# Schematic.net
KiCad netlist of a schematic drawn in Altium Designer
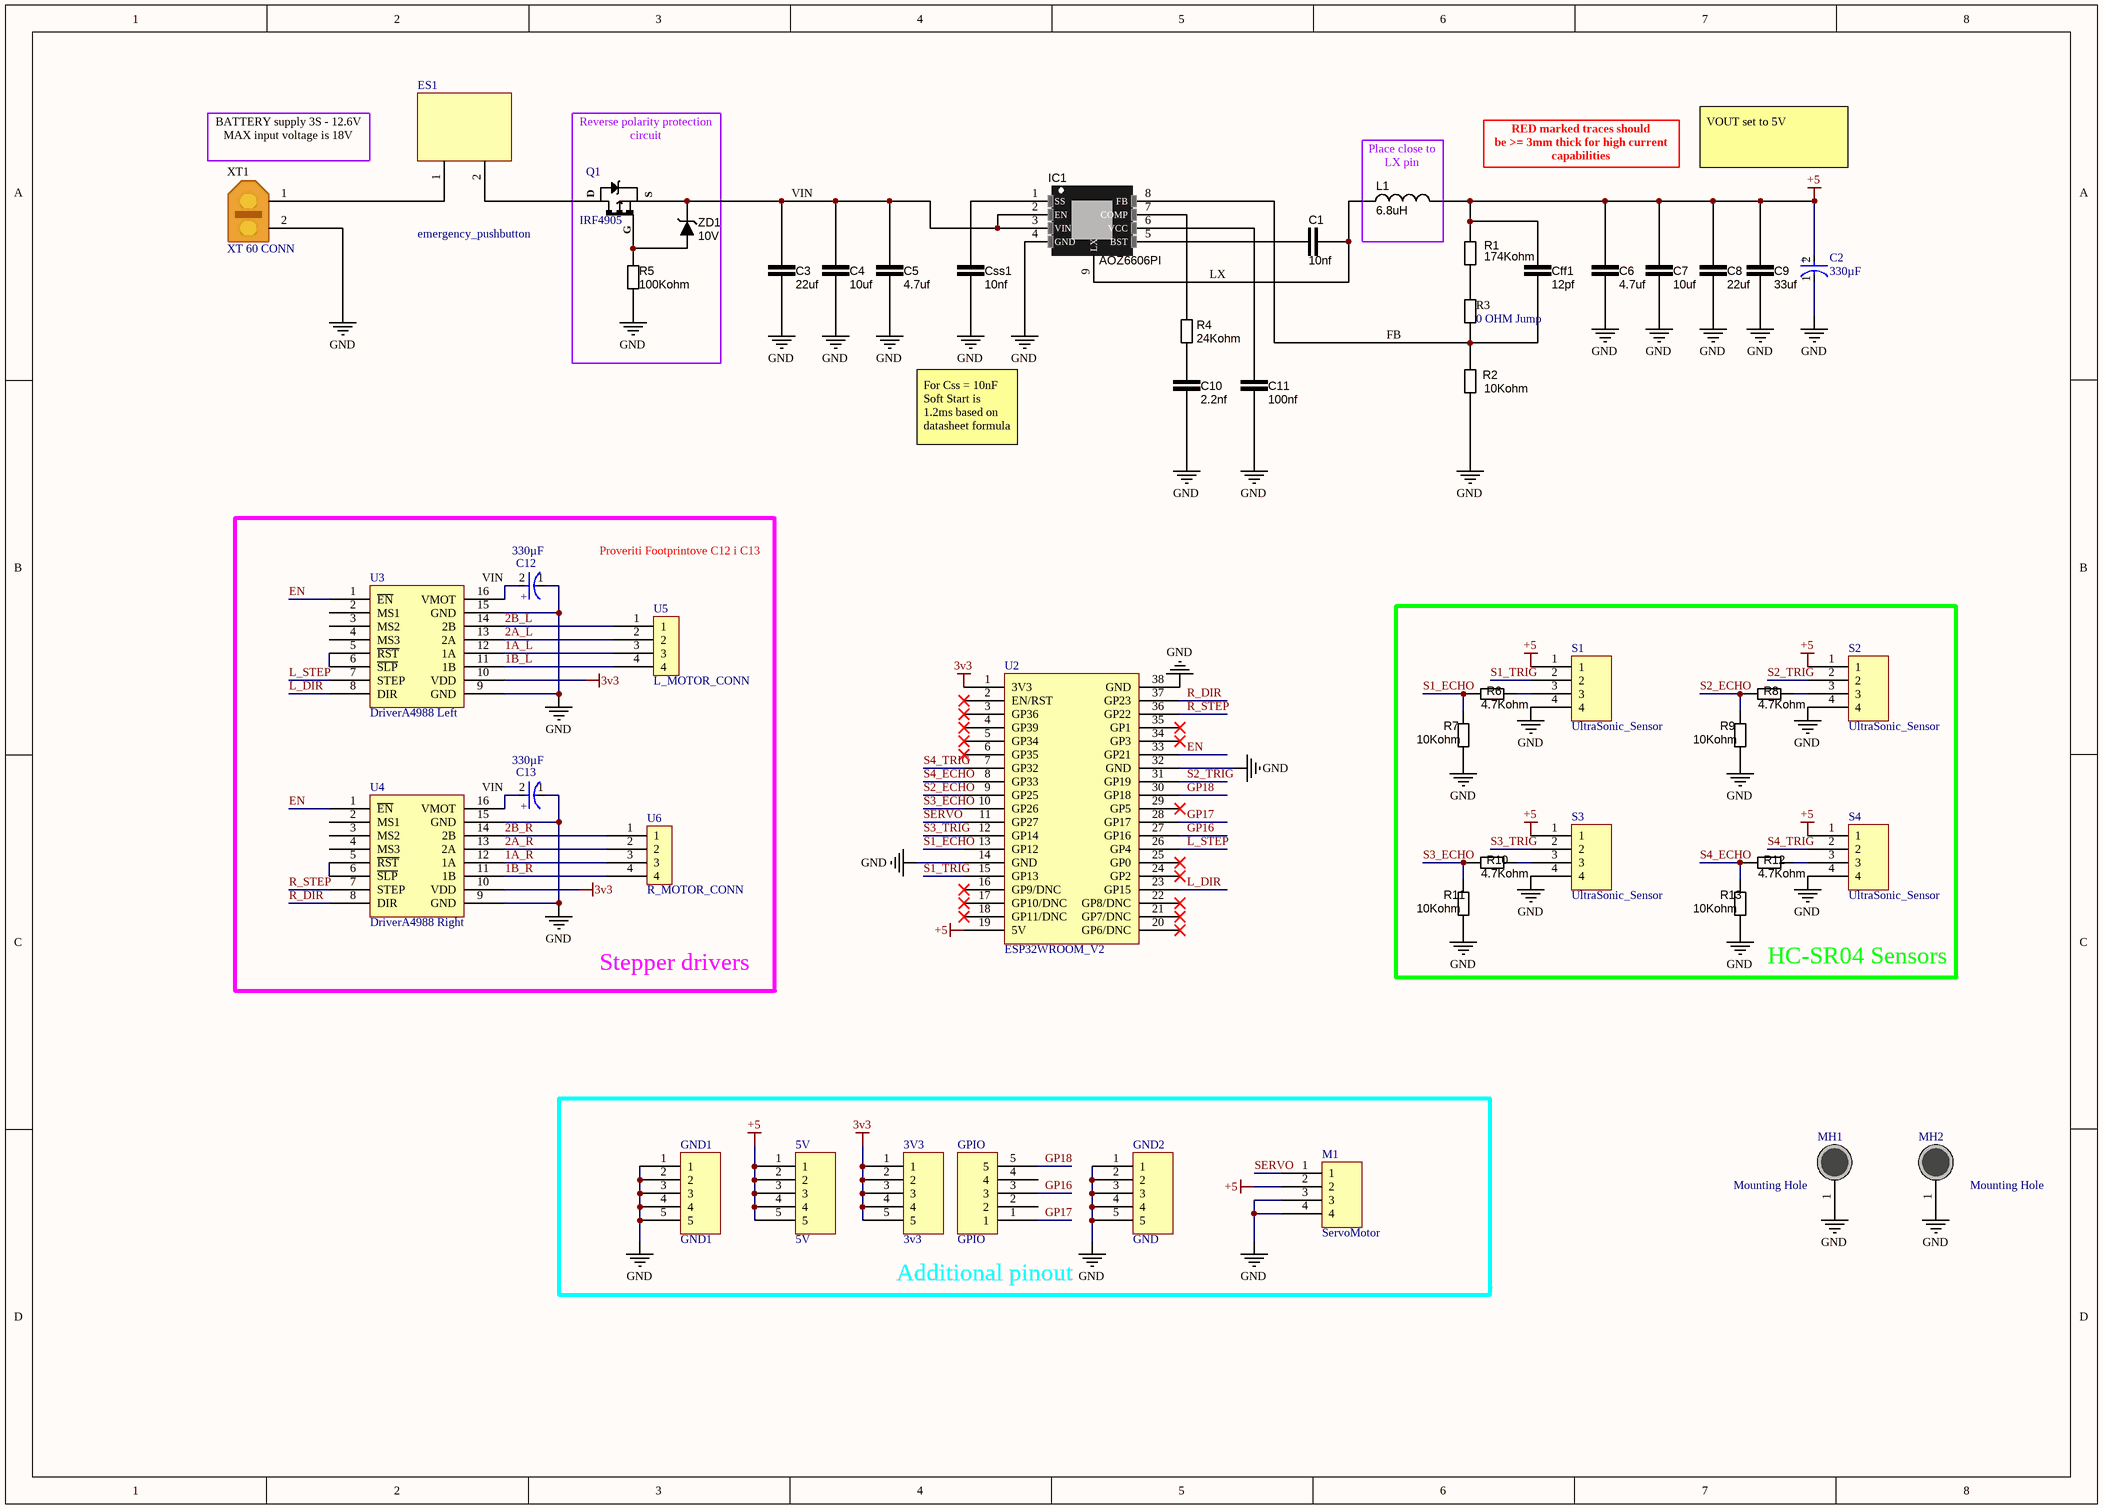
[diagram p0: Schematic.SchDoc]

(export (version "E")
  (design (tool "Eeschema 10.0.6"))
  (components
    (comp (ref "3V3")
      (value "3v3")
      (footprint "PIN_HEADER5")
      (description "5 pin header 100 mil")
      (libsource (lib "SIMA") (part "PIN_HEADER5"))
    )
    (comp (ref "5V")
      (value "5V")
      (footprint "PIN_HEADER5")
      (description "5 pin header 100 mils")
      (libsource (lib "SIMA") (part "PIN_HEADER5"))
    )
    (comp (ref "C1")
      (value "10nf")
      (footprint "CAP_0603")
      (description "CAP CER 10nF 0603 25V X7R")
      (libsource (lib "") (part "0000005_1"))
    )
    (comp (ref "C2")
      (value "330µF")
      (footprint "FP-FCG-MFG")
      (description "EEEFC1V331AP 330 uF, Aluminum Electrolytic Capacitor, 35 V, Radial Can - SMD")
      (fields (field (name "VOLTAGE") "35V") (field (name "TOLERANCE") "20%"))
      (libsource (lib "Altium Content Vault") (part "a00bbbee19879c290e62620ae7e47b1"))
    )
    (comp (ref "C3")
      (value "22uf")
      (footprint "CAP_0805")
      (description "CAP CER 22uF 0805 25V X5R")
      (libsource (lib "CapacitorsIntegrated") (part "0000001"))
    )
    (comp (ref "C4")
      (value "10uf")
      (footprint "CAP_0805")
      (description "CAP CER 10uF 0805 25V X5R")
      (libsource (lib "CapacitorsIntegrated") (part "0000002"))
    )
    (comp (ref "C5")
      (value "4.7uf")
      (footprint "CAP_0805")
      (description "CAP CER 4.7uF 0805 25V X5R")
      (libsource (lib "CapacitorsIntegrated") (part "0000003"))
    )
    (comp (ref "C6")
      (value "4.7uf")
      (footprint "CAP_0805")
      (description "CAP CER 4.7uF 0805 25V X5R")
      (libsource (lib "CapacitorsIntegrated") (part "0000003"))
    )
    (comp (ref "C7")
      (value "10uf")
      (footprint "CAP_0805")
      (description "CAP CER 10uF 0805 25V X5R")
      (libsource (lib "CapacitorsIntegrated") (part "0000002"))
    )
    (comp (ref "C8")
      (value "22uf")
      (footprint "CAP_0805")
      (description "CAP CER 22uF 0805 25V X5R")
      (libsource (lib "CapacitorsIntegrated") (part "0000001"))
    )
    (comp (ref "C9")
      (value "33uf")
      (footprint "CAP_1206")
      (description "CAP CER 33uF 1206 25V X5R")
      (libsource (lib "CapacitorsIntegrated") (part "0000004"))
    )
    (comp (ref "C10")
      (value "2.2nf")
      (footprint "CAP_0603")
      (description "CAP CER 2.2nF 0603 25V X7R")
      (libsource (lib "CapacitorsIntegrated") (part "0000006"))
    )
    (comp (ref "C11")
      (value "100nf")
      (footprint "CAP_0603")
      (description "CAP CER 100nF 0603 25V X7R")
      (libsource (lib "CapacitorsIntegrated") (part "0000007"))
    )
    (comp (ref "C12")
      (value "330µF")
      (footprint "FP-FCG-MFG")
      (description "EEEFC1V331AP 330 uF, Aluminum Electrolytic Capacitor, 35 V, Radial Can - SMD")
      (fields (field (name "VOLTAGE") "35V") (field (name "TOLERANCE") "20%"))
      (libsource (lib "Altium Content Vault") (part "a00bbbee19879c290e62620ae7e47b1"))
    )
    (comp (ref "C13")
      (value "330µF")
      (footprint "FP-FCG-MFG")
      (description "EEEFC1V331AP 330 uF, Aluminum Electrolytic Capacitor, 35 V, Radial Can - SMD")
      (fields (field (name "VOLTAGE") "35V") (field (name "TOLERANCE") "20%"))
      (libsource (lib "Altium Content Vault") (part "a00bbbee19879c290e62620ae7e47b1"))
    )
    (comp (ref "Cff1")
      (value "12pf")
      (footprint "CAP_0603")
      (description "CAP CER 12pF 0603 25V X7R")
      (libsource (lib "CapacitorsIntegrated") (part "0000008"))
    )
    (comp (ref "Css1")
      (value "10nf")
      (footprint "CAP_0603")
      (description "CAP CER 10nF 0603 25V X7R")
      (libsource (lib "CapacitorsIntegrated") (part "0000005"))
    )
    (comp (ref "ES1")
      (value "emergency_pushbutton")
      (footprint "emergency_footprint")
      (libsource (lib "SIMA") (part "emergency_pushbutton"))
    )
    (comp (ref "GND1")
      (value "GND1")
      (footprint "PIN_HEADER5")
      (description "5 pin header 100 mils")
      (libsource (lib "SIMA") (part "PIN_HEADER5"))
    )
    (comp (ref "GND2")
      (value "GND")
      (footprint "PIN_HEADER5")
      (description "5 pin header 100 mil")
      (libsource (lib "SIMA") (part "PIN_HEADER5"))
    )
    (comp (ref "GPIO")
      (value "GPIO")
      (footprint "PIN_HEADER5")
      (description "5 pin header 100 mil")
      (libsource (lib "") (part "PIN_HEADER5_1"))
    )
    (comp (ref "IC1")
      (value "AOZ6606PI")
      (footprint "SOP127P600X170_HS-9N")
      (description "Buck AOZ6606PI")
      (libsource (lib "IntegratedCircuits") (part "AOZ6606PI"))
    )
    (comp (ref "L1")
      (value "6.8uH")
      (footprint "INDM108103X40N")
      (description "IND 6.8uH 8A 23.3mOHM 13.5A ISAT")
      (libsource (lib "InductorIntegrated") (part "L000002"))
    )
    (comp (ref "M1")
      (value "ServoMotor")
      (footprint "UltraSonic_Sensor")
      (description "5 pin header 100 mil")
      (libsource (lib "SIMA") (part "UltraSonic_Sensor"))
    )
    (comp (ref "MH1")
      (value "Mounting Hole")
      (footprint "HOLE-3mm")
      (description "Mounting Hole 3mm")
      (libsource (lib "ElectroMechanical") (part "00000006"))
    )
    (comp (ref "MH2")
      (value "Mounting Hole")
      (footprint "HOLE-3mm")
      (description "Mounting Hole 3mm")
      (libsource (lib "ElectroMechanical") (part "00000006"))
    )
    (comp (ref "Q1")
      (value "IRF4905")
      (footprint "DPAK254P1524X483-3N")
      (fields
        (field (name "MANUFACTURER") "International Rectifier")
        (field (name "MANUFACTURER PART NUMBER") "IRF1404ZSPBF")
      )
      (libsource (lib "IntegratedCircuits") (part "IRF4905"))
    )
    (comp (ref "R1")
      (value "174Kohm")
      (footprint "RES_0603")
      (description "RES 174k OHM 0603 1/10W")
      (libsource (lib "ResistorsIntegrated") (part "R000003"))
    )
    (comp (ref "R2")
      (value "10Kohm")
      (footprint "RES_0603")
      (description "RES 10k OHM 0603 1/10W")
      (libsource (lib "") (part "R000001_2"))
    )
    (comp (ref "R3")
      (value "0 OHM Jump")
      (footprint "RES_0603")
      (description "RES 0 OHM JUMPER 1/10W 0603")
      (libsource (lib "ResistorsIntegrated") (part "R000007"))
    )
    (comp (ref "R4")
      (value "24Kohm")
      (footprint "RES_0603")
      (description "RES 24k OHM 0603 1/10W")
      (libsource (lib "ResistorsIntegrated") (part "R000005"))
    )
    (comp (ref "R5")
      (value "100Kohm")
      (footprint "RES_0603")
      (description "RES 100k OHM 0603 1/10W")
      (libsource (lib "ResistorsIntegrated") (part "R000006"))
    )
    (comp (ref "R6")
      (value "4.7Kohm")
      (footprint "RES_0603")
      (description "RES 4k7 OHM 0603 1/10W")
      (libsource (lib "") (part "R000001_1"))
    )
    (comp (ref "R7")
      (value "10Kohm")
      (footprint "RES_0603")
      (description "RES 10k OHM 0603 1/10W")
      (libsource (lib "ResistorsIntegrated") (part "R000001"))
    )
    (comp (ref "R8")
      (value "4.7Kohm")
      (footprint "RES_0603")
      (description "RES 4k7 OHM 0603 1/10W")
      (libsource (lib "") (part "R000001_1"))
    )
    (comp (ref "R9")
      (value "10Kohm")
      (footprint "RES_0603")
      (description "RES 10k OHM 0603 1/10W")
      (libsource (lib "ResistorsIntegrated") (part "R000001"))
    )
    (comp (ref "R10")
      (value "4.7Kohm")
      (footprint "RES_0603")
      (description "RES 4k7 OHM 0603 1/10W")
      (libsource (lib "") (part "R000001_1"))
    )
    (comp (ref "R11")
      (value "10Kohm")
      (footprint "RES_0603")
      (description "RES 10k OHM 0603 1/10W")
      (libsource (lib "ResistorsIntegrated") (part "R000001"))
    )
    (comp (ref "R12")
      (value "4.7Kohm")
      (footprint "RES_0603")
      (description "RES 4k7 OHM 0603 1/10W")
      (libsource (lib "") (part "R000001_1"))
    )
    (comp (ref "R13")
      (value "10Kohm")
      (footprint "RES_0603")
      (description "RES 10k OHM 0603 1/10W")
      (libsource (lib "ResistorsIntegrated") (part "R000001"))
    )
    (comp (ref "S1")
      (value "UltraSonic_Sensor")
      (footprint "UltraSonic_Sensor")
      (description "Connector onaj beli")
      (libsource (lib "SIMA") (part "UltraSonic_Sensor"))
    )
    (comp (ref "S2")
      (value "UltraSonic_Sensor")
      (footprint "UltraSonic_Sensor")
      (description "Connector onaj beli")
      (libsource (lib "SIMA") (part "UltraSonic_Sensor"))
    )
    (comp (ref "S3")
      (value "UltraSonic_Sensor")
      (footprint "UltraSonic_Sensor")
      (description "Connector onaj beli")
      (libsource (lib "SIMA") (part "UltraSonic_Sensor"))
    )
    (comp (ref "S4")
      (value "UltraSonic_Sensor")
      (footprint "UltraSonic_Sensor")
      (description "Connector onaj beli")
      (libsource (lib "SIMA") (part "UltraSonic_Sensor"))
    )
    (comp (ref "U2")
      (value "ESP32WROOM_V2")
      (footprint "ESP32WROOM")
      (description "Pinout Acine ESP32 Wroom plocice, pinovi poslagani po redu")
      (libsource (lib "SIMA") (part "ESP32WROOM_V2"))
    )
    (comp (ref "U3")
      (value "DriverA4988 Left")
      (footprint "DriverA4988")
      (description "Stepp Motor Driver")
      (libsource (lib "SIMA") (part "DriverA4988"))
    )
    (comp (ref "U4")
      (value "DriverA4988 Right")
      (footprint "DriverA4988")
      (description "Stepp Motor Driver")
      (libsource (lib "SIMA") (part "DriverA4988"))
    )
    (comp (ref "U5")
      (value "L_MOTOR_CONN")
      (footprint "STEP_MOTOR_CONN")
      (description "Connector onaj beli")
      (libsource (lib "SIMA") (part "STEP_MOTOR_CONN"))
    )
    (comp (ref "U6")
      (value "R_MOTOR_CONN")
      (footprint "STEP_MOTOR_CONN")
      (description "Connector onaj beli")
      (libsource (lib "SIMA") (part "STEP_MOTOR_CONN"))
    )
    (comp (ref "XT1")
      (value "XT 60 CONN")
      (footprint "XT60_CONN")
      (libsource (lib "SIMA") (part "XT60 CONN"))
    )
    (comp (ref "ZD1")
      (value "10V")
      (footprint "DIO_SMA")
      (description "Zener Diode 10 V 5 W ±5% Surface Mount SMC (DO-214AB)")
      (libsource (lib "IntegratedCircuits") (part "1SMA5931-AU_R1"))
    )
  )
  (nets
    (net (code "1") (name "+5") (class "Default")
      (node (ref "5V") (pin "1") (pinfunction "1_1") (pintype "passive"))
      (node (ref "5V") (pin "2") (pinfunction "2_2") (pintype "passive"))
      (node (ref "5V") (pin "3") (pinfunction "3_3") (pintype "passive"))
      (node (ref "5V") (pin "4") (pinfunction "4_4") (pintype "passive"))
      (node (ref "5V") (pin "5") (pinfunction "5_5") (pintype "passive"))
      (node (ref "C2") (pin "2") (pinfunction "A_2") (pintype "passive"))
      (node (ref "C6") (pin "2") (pinfunction "2_2") (pintype "passive"))
      (node (ref "C7") (pin "2") (pinfunction "2_2") (pintype "passive"))
      (node (ref "C8") (pin "2") (pinfunction "2_2") (pintype "passive"))
      (node (ref "C9") (pin "2") (pinfunction "2_2") (pintype "passive"))
      (node (ref "Cff1") (pin "2") (pinfunction "2_2") (pintype "passive"))
      (node (ref "L1") (pin "2") (pinfunction "2_2") (pintype "passive"))
      (node (ref "M1") (pin "2") (pinfunction "2_2") (pintype "passive"))
      (node (ref "R1") (pin "2") (pinfunction "2_2") (pintype "passive"))
      (node (ref "S1") (pin "1") (pinfunction "1_1") (pintype "passive"))
      (node (ref "S2") (pin "1") (pinfunction "1_1") (pintype "passive"))
      (node (ref "S3") (pin "1") (pinfunction "1_1") (pintype "passive"))
      (node (ref "S4") (pin "1") (pinfunction "1_1") (pintype "passive"))
      (node (ref "U2") (pin "19") (pinfunction "5V_19") (pintype "passive"))
    )
    (net (code "2") (name "/1A_L") (class "Default")
      (node (ref "U3") (pin "12") (pinfunction "1A_12") (pintype "passive"))
      (node (ref "U5") (pin "3") (pinfunction "3_3") (pintype "passive"))
    )
    (net (code "3") (name "/1A_R") (class "Default")
      (node (ref "U4") (pin "12") (pinfunction "1A_12") (pintype "passive"))
      (node (ref "U6") (pin "3") (pinfunction "3_3") (pintype "passive"))
    )
    (net (code "4") (name "/1B_L") (class "Default")
      (node (ref "U3") (pin "11") (pinfunction "1B_11") (pintype "passive"))
      (node (ref "U5") (pin "4") (pinfunction "4_4") (pintype "passive"))
    )
    (net (code "5") (name "/1B_R") (class "Default")
      (node (ref "U4") (pin "11") (pinfunction "1B_11") (pintype "passive"))
      (node (ref "U6") (pin "4") (pinfunction "4_4") (pintype "passive"))
    )
    (net (code "6") (name "/2A_L") (class "Default")
      (node (ref "U3") (pin "13") (pinfunction "2A_13") (pintype "passive"))
      (node (ref "U5") (pin "2") (pinfunction "2_2") (pintype "passive"))
    )
    (net (code "7") (name "/2A_R") (class "Default")
      (node (ref "U4") (pin "13") (pinfunction "2A_13") (pintype "passive"))
      (node (ref "U6") (pin "2") (pinfunction "2_2") (pintype "passive"))
    )
    (net (code "8") (name "/2B_L") (class "Default")
      (node (ref "U3") (pin "14") (pinfunction "2B_14") (pintype "passive"))
      (node (ref "U5") (pin "1") (pinfunction "1_1") (pintype "passive"))
    )
    (net (code "9") (name "/2B_R") (class "Default")
      (node (ref "U4") (pin "14") (pinfunction "2B_14") (pintype "passive"))
      (node (ref "U6") (pin "1") (pinfunction "1_1") (pintype "passive"))
    )
    (net (code "10") (name "/EN") (class "Default")
      (node (ref "U2") (pin "33") (pinfunction "GP21_33") (pintype "passive"))
      (node (ref "U3") (pin "1") (pinfunction "~{EN}_1") (pintype "passive"))
      (node (ref "U4") (pin "1") (pinfunction "~{EN}_1") (pintype "passive"))
    )
    (net (code "11") (name "/FB") (class "Default")
      (node (ref "Cff1") (pin "1") (pinfunction "1_1") (pintype "passive"))
      (node (ref "IC1") (pin "8") (pinfunction "FB_8") (pintype "passive"))
      (node (ref "R2") (pin "2") (pinfunction "2_2") (pintype "passive"))
      (node (ref "R3") (pin "1") (pinfunction "1_1") (pintype "passive"))
    )
    (net (code "12") (name "/GP16") (class "Default")
      (node (ref "GPIO") (pin "3") (pinfunction "3_3") (pintype "passive"))
      (node (ref "U2") (pin "27") (pinfunction "GP16_27") (pintype "passive"))
    )
    (net (code "13") (name "/GP17") (class "Default")
      (node (ref "GPIO") (pin "1") (pinfunction "1_1") (pintype "passive"))
      (node (ref "U2") (pin "28") (pinfunction "GP17_28") (pintype "passive"))
    )
    (net (code "14") (name "/GP18") (class "Default")
      (node (ref "GPIO") (pin "5") (pinfunction "5_5") (pintype "passive"))
      (node (ref "U2") (pin "30") (pinfunction "GP18_30") (pintype "passive"))
    )
    (net (code "15") (name "/LX") (class "Default")
      (node (ref "C1") (pin "2") (pinfunction "2_2") (pintype "passive"))
      (node (ref "IC1") (pin "9") (pinfunction "LX_9") (pintype "passive"))
      (node (ref "L1") (pin "1") (pinfunction "1_1") (pintype "passive"))
    )
    (net (code "16") (name "/L_DIR") (class "Default")
      (node (ref "U2") (pin "23") (pinfunction "GP15_23") (pintype "passive"))
      (node (ref "U3") (pin "8") (pinfunction "DIR_8") (pintype "passive"))
    )
    (net (code "17") (name "/L_STEP") (class "Default")
      (node (ref "U2") (pin "26") (pinfunction "GP4_26") (pintype "passive"))
      (node (ref "U3") (pin "7") (pinfunction "STEP_7") (pintype "passive"))
    )
    (net (code "18") (name "/R_DIR") (class "Default")
      (node (ref "U2") (pin "37") (pinfunction "GP23_37") (pintype "passive"))
      (node (ref "U4") (pin "8") (pinfunction "DIR_8") (pintype "passive"))
    )
    (net (code "19") (name "/R_STEP") (class "Default")
      (node (ref "U2") (pin "36") (pinfunction "GP22_36") (pintype "passive"))
      (node (ref "U4") (pin "7") (pinfunction "STEP_7") (pintype "passive"))
    )
    (net (code "20") (name "/S1_ECHO") (class "Default")
      (node (ref "R6") (pin "1") (pinfunction "1_1") (pintype "passive"))
      (node (ref "R7") (pin "1") (pinfunction "1_1") (pintype "passive"))
      (node (ref "U2") (pin "13") (pinfunction "GP12_13") (pintype "passive"))
    )
    (net (code "21") (name "/S1_TRIG") (class "Default")
      (node (ref "S1") (pin "2") (pinfunction "2_2") (pintype "passive"))
      (node (ref "U2") (pin "15") (pinfunction "GP13_15") (pintype "passive"))
    )
    (net (code "22") (name "/S2_ECHO") (class "Default")
      (node (ref "R8") (pin "1") (pinfunction "1_1") (pintype "passive"))
      (node (ref "R9") (pin "1") (pinfunction "1_1") (pintype "passive"))
      (node (ref "U2") (pin "9") (pinfunction "GP25_9") (pintype "passive"))
    )
    (net (code "23") (name "/S2_TRIG") (class "Default")
      (node (ref "S2") (pin "2") (pinfunction "2_2") (pintype "passive"))
      (node (ref "U2") (pin "31") (pinfunction "GP19_31") (pintype "passive"))
    )
    (net (code "24") (name "/S3_ECHO") (class "Default")
      (node (ref "R10") (pin "1") (pinfunction "1_1") (pintype "passive"))
      (node (ref "R11") (pin "1") (pinfunction "1_1") (pintype "passive"))
      (node (ref "U2") (pin "10") (pinfunction "GP26_10") (pintype "passive"))
    )
    (net (code "25") (name "/S3_TRIG") (class "Default")
      (node (ref "S3") (pin "2") (pinfunction "2_2") (pintype "passive"))
      (node (ref "U2") (pin "12") (pinfunction "GP14_12") (pintype "passive"))
    )
    (net (code "26") (name "/S4_ECHO") (class "Default")
      (node (ref "R12") (pin "1") (pinfunction "1_1") (pintype "passive"))
      (node (ref "R13") (pin "1") (pinfunction "1_1") (pintype "passive"))
      (node (ref "U2") (pin "8") (pinfunction "GP33_8") (pintype "passive"))
    )
    (net (code "27") (name "/S4_TRIG") (class "Default")
      (node (ref "S4") (pin "2") (pinfunction "2_2") (pintype "passive"))
      (node (ref "U2") (pin "7") (pinfunction "GP32_7") (pintype "passive"))
    )
    (net (code "28") (name "/SERVO") (class "Default")
      (node (ref "M1") (pin "1") (pinfunction "1_1") (pintype "passive"))
      (node (ref "U2") (pin "11") (pinfunction "GP27_11") (pintype "passive"))
    )
    (net (code "29") (name "/VIN") (class "Default")
      (node (ref "C12") (pin "2") (pinfunction "A_2") (pintype "passive"))
      (node (ref "C13") (pin "2") (pinfunction "A_2") (pintype "passive"))
      (node (ref "C3") (pin "2") (pinfunction "2_2") (pintype "passive"))
      (node (ref "C4") (pin "2") (pinfunction "2_2") (pintype "passive"))
      (node (ref "C5") (pin "2") (pinfunction "2_2") (pintype "passive"))
      (node (ref "IC1") (pin "2") (pinfunction "EN_2") (pintype "passive"))
      (node (ref "IC1") (pin "3") (pinfunction "VIN_3") (pintype "passive"))
      (node (ref "Q1") (pin "3") (pinfunction "3_3") (pintype "passive"))
      (node (ref "U3") (pin "16") (pinfunction "VMOT_16") (pintype "passive"))
      (node (ref "U4") (pin "16") (pinfunction "VMOT_16") (pintype "passive"))
      (node (ref "ZD1") (pin "1") (pinfunction "Cathode_1") (pintype "passive"))
    )
    (net (code "30") (name "3v3") (class "Default")
      (node (ref "3V3") (pin "1") (pinfunction "1_1") (pintype "passive"))
      (node (ref "3V3") (pin "2") (pinfunction "2_2") (pintype "passive"))
      (node (ref "3V3") (pin "3") (pinfunction "3_3") (pintype "passive"))
      (node (ref "3V3") (pin "4") (pinfunction "4_4") (pintype "passive"))
      (node (ref "3V3") (pin "5") (pinfunction "5_5") (pintype "passive"))
      (node (ref "U2") (pin "1") (pinfunction "3V3_1") (pintype "passive"))
      (node (ref "U3") (pin "10") (pinfunction "VDD_10") (pintype "passive"))
      (node (ref "U4") (pin "10") (pinfunction "VDD_10") (pintype "passive"))
    )
    (net (code "31") (name "GND") (class "Default")
      (node (ref "C10") (pin "1") (pinfunction "1_1") (pintype "passive"))
      (node (ref "C11") (pin "1") (pinfunction "1_1") (pintype "passive"))
      (node (ref "C12") (pin "1") (pinfunction "C_1") (pintype "passive"))
      (node (ref "C13") (pin "1") (pinfunction "C_1") (pintype "passive"))
      (node (ref "C2") (pin "1") (pinfunction "C_1") (pintype "passive"))
      (node (ref "C3") (pin "1") (pinfunction "1_1") (pintype "passive"))
      (node (ref "C4") (pin "1") (pinfunction "1_1") (pintype "passive"))
      (node (ref "C5") (pin "1") (pinfunction "1_1") (pintype "passive"))
      (node (ref "C6") (pin "1") (pinfunction "1_1") (pintype "passive"))
      (node (ref "C7") (pin "1") (pinfunction "1_1") (pintype "passive"))
      (node (ref "C8") (pin "1") (pinfunction "1_1") (pintype "passive"))
      (node (ref "C9") (pin "1") (pinfunction "1_1") (pintype "passive"))
      (node (ref "Css1") (pin "1") (pinfunction "1_1") (pintype "passive"))
      (node (ref "GND1") (pin "1") (pinfunction "1_1") (pintype "passive"))
      (node (ref "GND1") (pin "2") (pinfunction "2_2") (pintype "passive"))
      (node (ref "GND1") (pin "3") (pinfunction "3_3") (pintype "passive"))
      (node (ref "GND1") (pin "4") (pinfunction "4_4") (pintype "passive"))
      (node (ref "GND1") (pin "5") (pinfunction "5_5") (pintype "passive"))
      (node (ref "GND2") (pin "1") (pinfunction "1_1") (pintype "passive"))
      (node (ref "GND2") (pin "2") (pinfunction "2_2") (pintype "passive"))
      (node (ref "GND2") (pin "3") (pinfunction "3_3") (pintype "passive"))
      (node (ref "GND2") (pin "4") (pinfunction "4_4") (pintype "passive"))
      (node (ref "GND2") (pin "5") (pinfunction "5_5") (pintype "passive"))
      (node (ref "IC1") (pin "4") (pinfunction "GND_4") (pintype "passive"))
      (node (ref "M1") (pin "3") (pinfunction "3_3") (pintype "passive"))
      (node (ref "M1") (pin "4") (pinfunction "4_4") (pintype "passive"))
      (node (ref "MH1") (pin "1") (pinfunction "1_1") (pintype "passive"))
      (node (ref "MH2") (pin "1") (pinfunction "1_1") (pintype "passive"))
      (node (ref "R11") (pin "2") (pinfunction "2_2") (pintype "passive"))
      (node (ref "R13") (pin "2") (pinfunction "2_2") (pintype "passive"))
      (node (ref "R2") (pin "1") (pinfunction "1_1") (pintype "passive"))
      (node (ref "R5") (pin "1") (pinfunction "1_1") (pintype "passive"))
      (node (ref "R7") (pin "2") (pinfunction "2_2") (pintype "passive"))
      (node (ref "R9") (pin "2") (pinfunction "2_2") (pintype "passive"))
      (node (ref "S1") (pin "4") (pinfunction "4_4") (pintype "passive"))
      (node (ref "S2") (pin "4") (pinfunction "4_4") (pintype "passive"))
      (node (ref "S3") (pin "4") (pinfunction "4_4") (pintype "passive"))
      (node (ref "S4") (pin "4") (pinfunction "4_4") (pintype "passive"))
      (node (ref "U2") (pin "14") (pinfunction "GND_14") (pintype "passive"))
      (node (ref "U2") (pin "32") (pinfunction "GND_32") (pintype "passive"))
      (node (ref "U2") (pin "38") (pinfunction "GND_38") (pintype "passive"))
      (node (ref "U3") (pin "15") (pinfunction "GND_15") (pintype "passive"))
      (node (ref "U3") (pin "9") (pinfunction "GND_9") (pintype "passive"))
      (node (ref "U4") (pin "15") (pinfunction "GND_15") (pintype "passive"))
      (node (ref "U4") (pin "9") (pinfunction "GND_9") (pintype "passive"))
      (node (ref "XT1") (pin "2") (pinfunction "2_2") (pintype "passive"))
    )
    (net (code "32") (name "Net-(C10-Pad2)") (class "Default")
      (node (ref "C10") (pin "2") (pinfunction "2_2") (pintype "passive"))
      (node (ref "R4") (pin "1") (pinfunction "1_1") (pintype "passive"))
    )
    (net (code "33") (name "Net-(ES1-7)") (class "Default")
      (node (ref "ES1") (pin "2") (pinfunction "7_2") (pintype "passive"))
      (node (ref "Q1") (pin "4") (pinfunction "4_4") (pintype "passive"))
    )
    (net (code "34") (name "Net-(ES1-8)") (class "Default")
      (node (ref "ES1") (pin "1") (pinfunction "8_1") (pintype "passive"))
      (node (ref "XT1") (pin "1") (pinfunction "1_1") (pintype "passive"))
    )
    (net (code "35") (name "Net-(IC1-BST)") (class "Default")
      (node (ref "C1") (pin "1") (pinfunction "1_1") (pintype "passive"))
      (node (ref "IC1") (pin "5") (pinfunction "BST_5") (pintype "passive"))
    )
    (net (code "36") (name "Net-(IC1-COMP)") (class "Default")
      (node (ref "IC1") (pin "7") (pinfunction "COMP_7") (pintype "passive"))
      (node (ref "R4") (pin "2") (pinfunction "2_2") (pintype "passive"))
    )
    (net (code "37") (name "Net-(IC1-SS)") (class "Default")
      (node (ref "Css1") (pin "2") (pinfunction "2_2") (pintype "passive"))
      (node (ref "IC1") (pin "1") (pinfunction "SS_1") (pintype "passive"))
    )
    (net (code "38") (name "Net-(IC1-VCC)") (class "Default")
      (node (ref "C11") (pin "2") (pinfunction "2_2") (pintype "passive"))
      (node (ref "IC1") (pin "6") (pinfunction "VCC_6") (pintype "passive"))
    )
    (net (code "39") (name "Net-(Q1-G)") (class "Default")
      (node (ref "Q1") (pin "1") (pinfunction "G_1") (pintype "passive"))
      (node (ref "R5") (pin "2") (pinfunction "2_2") (pintype "passive"))
      (node (ref "ZD1") (pin "2") (pinfunction "Anode_2") (pintype "passive"))
    )
    (net (code "40") (name "Net-(R1-Pad1)") (class "Default")
      (node (ref "R1") (pin "1") (pinfunction "1_1") (pintype "passive"))
      (node (ref "R3") (pin "2") (pinfunction "2_2") (pintype "passive"))
    )
    (net (code "41") (name "Net-(R6-Pad2)") (class "Default")
      (node (ref "R6") (pin "2") (pinfunction "2_2") (pintype "passive"))
      (node (ref "S1") (pin "3") (pinfunction "3_3") (pintype "passive"))
    )
    (net (code "42") (name "Net-(R8-Pad2)") (class "Default")
      (node (ref "R8") (pin "2") (pinfunction "2_2") (pintype "passive"))
      (node (ref "S2") (pin "3") (pinfunction "3_3") (pintype "passive"))
    )
    (net (code "43") (name "Net-(R10-Pad2)") (class "Default")
      (node (ref "R10") (pin "2") (pinfunction "2_2") (pintype "passive"))
      (node (ref "S3") (pin "3") (pinfunction "3_3") (pintype "passive"))
    )
    (net (code "44") (name "Net-(R12-Pad2)") (class "Default")
      (node (ref "R12") (pin "2") (pinfunction "2_2") (pintype "passive"))
      (node (ref "S4") (pin "3") (pinfunction "3_3") (pintype "passive"))
    )
    (net (code "45") (name "Net-(U3-~{RST})") (class "Default")
      (node (ref "U3") (pin "5") (pinfunction "~{RST}_5") (pintype "passive"))
      (node (ref "U3") (pin "6") (pinfunction "~{SLP}_6") (pintype "passive"))
    )
    (net (code "46") (name "Net-(U4-~{RST})") (class "Default")
      (node (ref "U4") (pin "5") (pinfunction "~{RST}_5") (pintype "passive"))
      (node (ref "U4") (pin "6") (pinfunction "~{SLP}_6") (pintype "passive"))
    )
    (net (code "47") (name "unconnected-(GPIO-Pad2)") (class "Default")
      (node (ref "GPIO") (pin "2") (pinfunction "2_2") (pintype "passive"))
    )
    (net (code "48") (name "unconnected-(GPIO-Pad4)") (class "Default")
      (node (ref "GPIO") (pin "4") (pinfunction "4_4") (pintype "passive"))
    )
    (net (code "49") (name "unconnected-(U2-EN{slash}RST-Pad2)") (class "Default")
      (node (ref "U2") (pin "2") (pinfunction "EN/RST_2") (pintype "passive+no_connect"))
    )
    (net (code "50") (name "unconnected-(U2-GP0-Pad25)") (class "Default")
      (node (ref "U2") (pin "25") (pinfunction "GP0_25") (pintype "passive+no_connect"))
    )
    (net (code "51") (name "unconnected-(U2-GP1-Pad35)") (class "Default")
      (node (ref "U2") (pin "35") (pinfunction "GP1_35") (pintype "passive+no_connect"))
    )
    (net (code "52") (name "unconnected-(U2-GP2-Pad24)") (class "Default")
      (node (ref "U2") (pin "24") (pinfunction "GP2_24") (pintype "passive+no_connect"))
    )
    (net (code "53") (name "unconnected-(U2-GP3-Pad34)") (class "Default")
      (node (ref "U2") (pin "34") (pinfunction "GP3_34") (pintype "passive+no_connect"))
    )
    (net (code "54") (name "unconnected-(U2-GP5-Pad29)") (class "Default")
      (node (ref "U2") (pin "29") (pinfunction "GP5_29") (pintype "passive+no_connect"))
    )
    (net (code "55") (name "unconnected-(U2-GP6{slash}DNC-Pad20)") (class "Default")
      (node (ref "U2") (pin "20") (pinfunction "GP6/DNC_20") (pintype "passive+no_connect"))
    )
    (net (code "56") (name "unconnected-(U2-GP7{slash}DNC-Pad21)") (class "Default")
      (node (ref "U2") (pin "21") (pinfunction "GP7/DNC_21") (pintype "passive+no_connect"))
    )
    (net (code "57") (name "unconnected-(U2-GP8{slash}DNC-Pad22)") (class "Default")
      (node (ref "U2") (pin "22") (pinfunction "GP8/DNC_22") (pintype "passive+no_connect"))
    )
    (net (code "58") (name "unconnected-(U2-GP9{slash}DNC-Pad16)") (class "Default")
      (node (ref "U2") (pin "16") (pinfunction "GP9/DNC_16") (pintype "passive+no_connect"))
    )
    (net (code "59") (name "unconnected-(U2-GP10{slash}DNC-Pad17)") (class "Default")
      (node (ref "U2") (pin "17") (pinfunction "GP10/DNC_17") (pintype "passive+no_connect"))
    )
    (net (code "60") (name "unconnected-(U2-GP11{slash}DNC-Pad18)") (class "Default")
      (node (ref "U2") (pin "18") (pinfunction "GP11/DNC_18") (pintype "passive+no_connect"))
    )
    (net (code "61") (name "unconnected-(U2-GP34-Pad5)") (class "Default")
      (node (ref "U2") (pin "5") (pinfunction "GP34_5") (pintype "passive+no_connect"))
    )
    (net (code "62") (name "unconnected-(U2-GP35-Pad6)") (class "Default")
      (node (ref "U2") (pin "6") (pinfunction "GP35_6") (pintype "passive+no_connect"))
    )
    (net (code "63") (name "unconnected-(U2-GP36-Pad3)") (class "Default")
      (node (ref "U2") (pin "3") (pinfunction "GP36_3") (pintype "passive+no_connect"))
    )
    (net (code "64") (name "unconnected-(U2-GP39-Pad4)") (class "Default")
      (node (ref "U2") (pin "4") (pinfunction "GP39_4") (pintype "passive+no_connect"))
    )
    (net (code "65") (name "unconnected-(U3-MS1-Pad2)") (class "Default")
      (node (ref "U3") (pin "2") (pinfunction "MS1_2") (pintype "passive"))
    )
    (net (code "66") (name "unconnected-(U3-MS2-Pad3)") (class "Default")
      (node (ref "U3") (pin "3") (pinfunction "MS2_3") (pintype "passive"))
    )
    (net (code "67") (name "unconnected-(U3-MS3-Pad4)") (class "Default")
      (node (ref "U3") (pin "4") (pinfunction "MS3_4") (pintype "passive"))
    )
    (net (code "68") (name "unconnected-(U4-MS1-Pad2)") (class "Default")
      (node (ref "U4") (pin "2") (pinfunction "MS1_2") (pintype "passive"))
    )
    (net (code "69") (name "unconnected-(U4-MS2-Pad3)") (class "Default")
      (node (ref "U4") (pin "3") (pinfunction "MS2_3") (pintype "passive"))
    )
    (net (code "70") (name "unconnected-(U4-MS3-Pad4)") (class "Default")
      (node (ref "U4") (pin "4") (pinfunction "MS3_4") (pintype "passive"))
    )
  )
)
